# Sheet2.net
KiCad netlist of a schematic drawn in Altium Designer
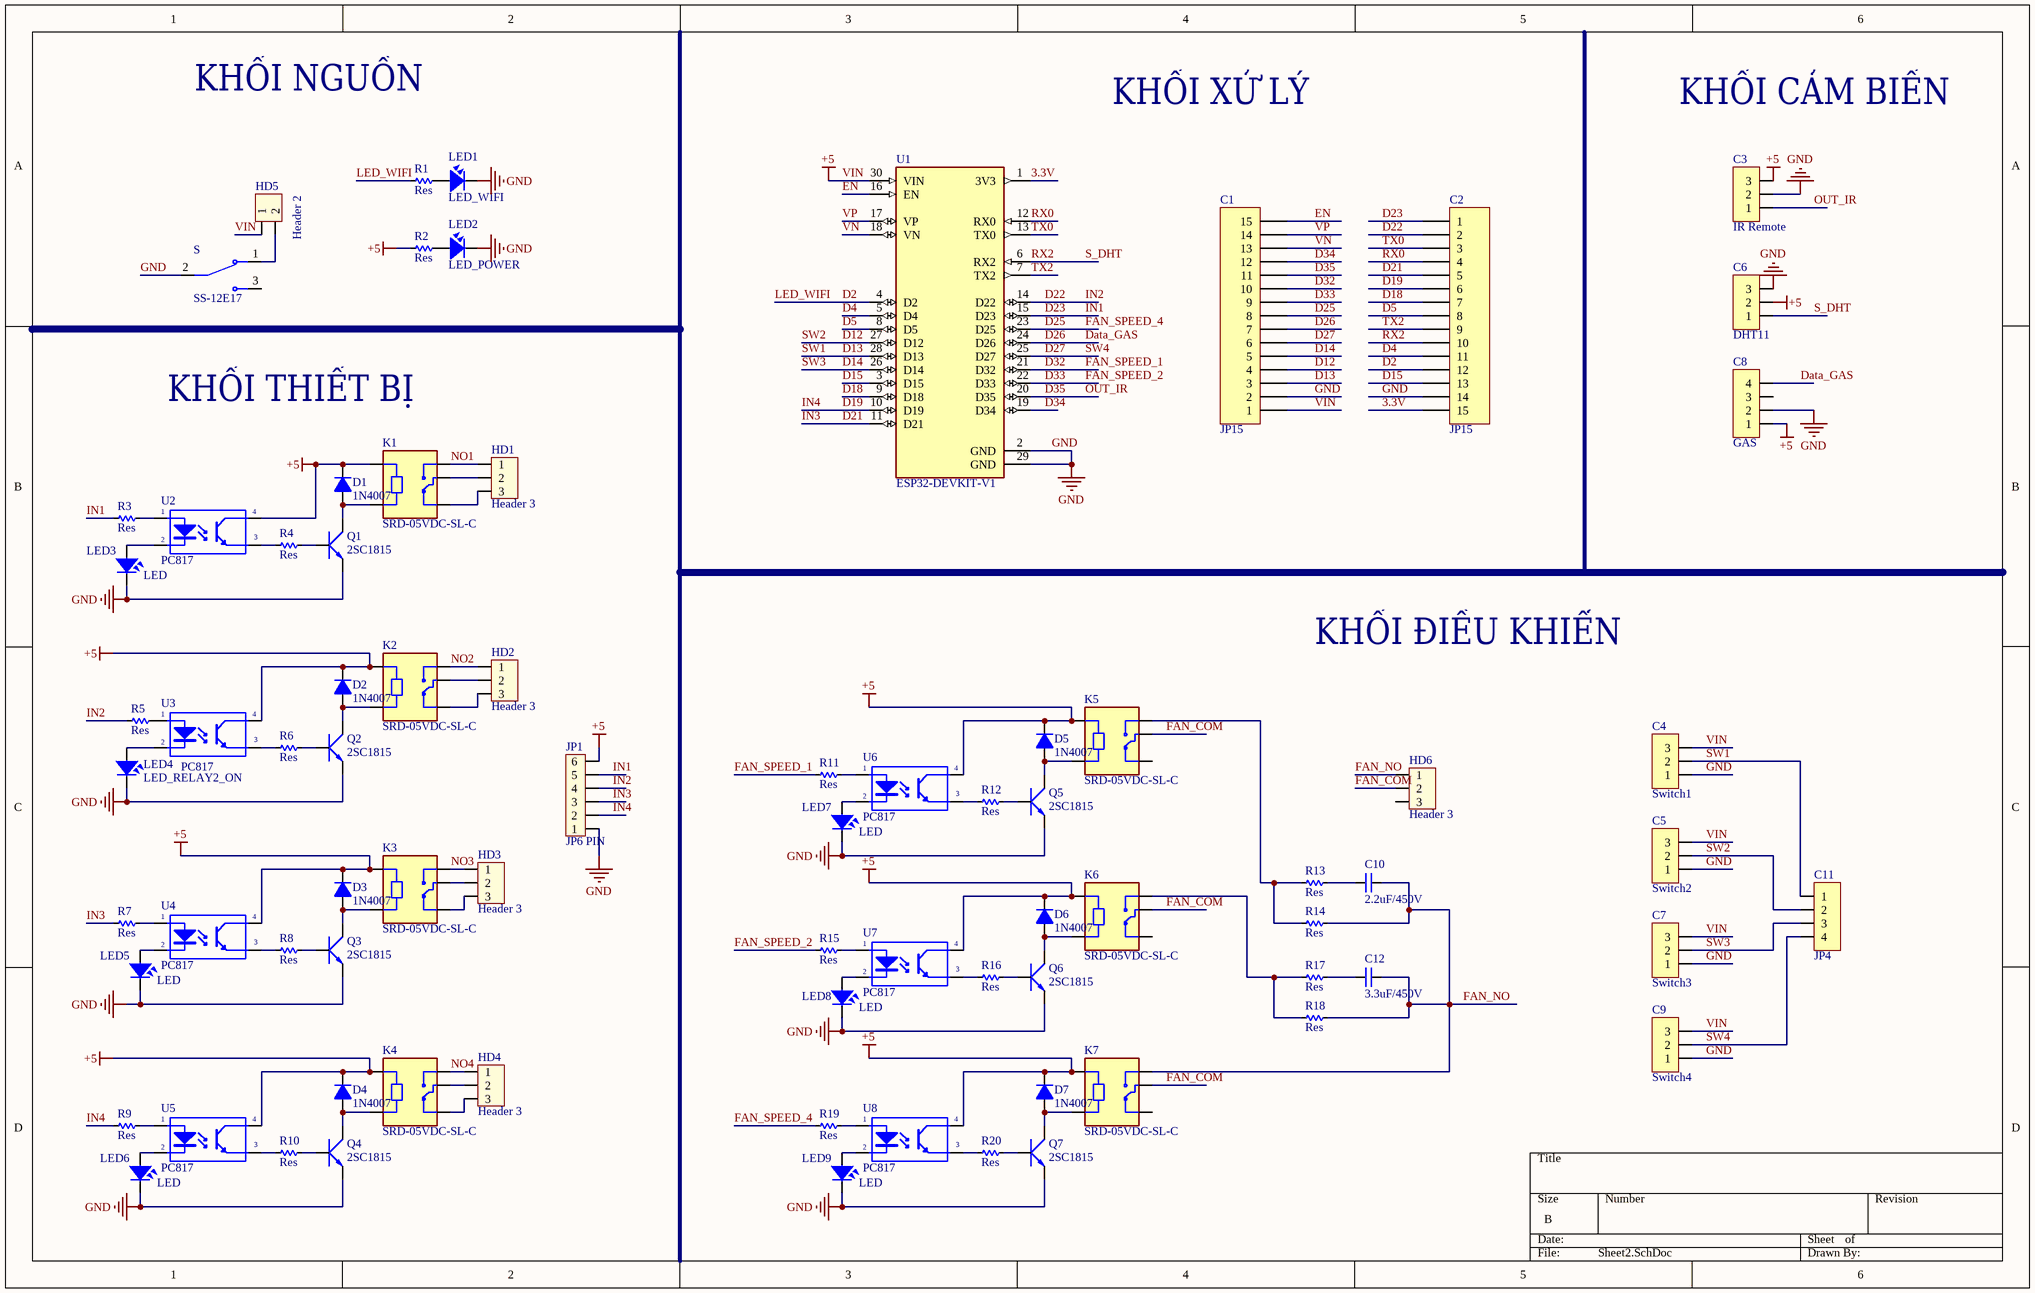
[diagram p0: Sheet2.SchDoc]

(export (version "E")
  (design (tool "Eeschema 10.0.6"))
  (components
    (comp (ref "C1")
      (value "JP15")
      (footprint "JP15-C1T")
      (description "WR-PHD 2.54 mm Angled Socket Header")
      (fields
        (field (name "MANUFACTURER") "Würth Elektronik eiSos GmbH")
        (field (name "PARTNO") "613015143121")
        (field (name "CREATED BY") "Karrer Zheng")
      )
      (libsource (lib "TechMT.VN_Lib_Project v2") (part "JP15"))
    )
    (comp (ref "C2")
      (value "JP15")
      (footprint "JP15-C1T")
      (description "WR-PHD 2.54 mm Angled Socket Header")
      (fields
        (field (name "MANUFACTURER") "Würth Elektronik eiSos GmbH")
        (field (name "PARTNO") "613015143121")
        (field (name "CREATED BY") "Karrer Zheng")
      )
      (libsource (lib "") (part "JP15_1"))
    )
    (comp (ref "C3")
      (value "IR Remote")
      (footprint "JP3-C1T")
      (description "WR-PHD 2.54 mm Angled Socket Header")
      (fields
        (field (name "MANUFACTURER") "Würth Elektronik eiSos GmbH")
        (field (name "PARTNO") "613003143121")
        (field (name "CREATED BY") "Karrer Zheng")
      )
      (libsource (lib "TechMT.VN_Lib_Project v2") (part "JP3"))
    )
    (comp (ref "C4")
      (value "Switch1")
      (footprint "JP3-C1T")
      (description "WR-PHD 2.54 mm Angled Socket Header")
      (fields
        (field (name "MANUFACTURER") "Würth Elektronik eiSos GmbH")
        (field (name "PARTNO") "613003143121")
        (field (name "CREATED BY") "Karrer Zheng")
      )
      (libsource (lib "TechMT.VN_Lib_Project v2") (part "JP3"))
    )
    (comp (ref "C5")
      (value "Switch2")
      (footprint "JP3-C1T")
      (description "WR-PHD 2.54 mm Angled Socket Header")
      (fields
        (field (name "MANUFACTURER") "Würth Elektronik eiSos GmbH")
        (field (name "PARTNO") "613003143121")
        (field (name "CREATED BY") "Karrer Zheng")
      )
      (libsource (lib "TechMT.VN_Lib_Project v2") (part "JP3"))
    )
    (comp (ref "C6")
      (value "DHT11")
      (footprint "JP3-C1T")
      (description "WR-PHD 2.54 mm Angled Socket Header")
      (fields
        (field (name "MANUFACTURER") "Würth Elektronik eiSos GmbH")
        (field (name "PARTNO") "613003143121")
        (field (name "CREATED BY") "Karrer Zheng")
      )
      (libsource (lib "TechMT.VN_Lib_Project v2") (part "JP3"))
    )
    (comp (ref "C7")
      (value "Switch3")
      (footprint "JP3-C1T")
      (description "WR-PHD 2.54 mm Angled Socket Header")
      (fields
        (field (name "MANUFACTURER") "Würth Elektronik eiSos GmbH")
        (field (name "PARTNO") "613003143121")
        (field (name "CREATED BY") "Karrer Zheng")
      )
      (libsource (lib "TechMT.VN_Lib_Project v2") (part "JP3"))
    )
    (comp (ref "C8")
      (value "GAS")
      (footprint "JP4-C1T")
      (description "WR-PHD 2.54 mm Angled Socket Header")
      (fields
        (field (name "MANUFACTURER") "Würth Elektronik eiSos GmbH")
        (field (name "PARTNO") "613004143121")
        (field (name "CREATED BY") "Karrer Zheng")
      )
      (libsource (lib "TechMT.VN_Lib_Project v2") (part "JP4"))
    )
    (comp (ref "C9")
      (value "Switch4")
      (footprint "JP3-C1T")
      (description "WR-PHD 2.54 mm Angled Socket Header")
      (fields
        (field (name "MANUFACTURER") "Würth Elektronik eiSos GmbH")
        (field (name "PARTNO") "613003143121")
        (field (name "CREATED BY") "Karrer Zheng")
      )
      (libsource (lib "TechMT.VN_Lib_Project v2") (part "JP3"))
    )
    (comp (ref "C10")
      (value "2.2uF/450V")
      (footprint "Capacitor_CBB")
      (description "Cap 10000uF/63V")
      (libsource (lib "syhaunguyen") (part "CP9"))
    )
    (comp (ref "C11")
      (value "JP4")
      (footprint "JP4-C1T")
      (description "WR-PHD 2.54 mm Angled Socket Header")
      (fields
        (field (name "MANUFACTURER") "Würth Elektronik eiSos GmbH")
        (field (name "PARTNO") "613004143121")
        (field (name "CREATED BY") "Karrer Zheng")
      )
      (libsource (lib "") (part "JP4_1"))
    )
    (comp (ref "C12")
      (value "3.3uF/450V")
      (footprint "Capacitor_CBB")
      (description "Cap 10000uF/63V")
      (libsource (lib "syhaunguyen") (part "CP9"))
    )
    (comp (ref "D1")
      (value "1N4007")
      (footprint "D1A")
      (description "Diode 1A")
      (libsource (lib "syhaunguyen") (part "D1A"))
    )
    (comp (ref "D2")
      (value "1N4007")
      (footprint "D1A")
      (description "Diode 1A")
      (libsource (lib "syhaunguyen") (part "D1A"))
    )
    (comp (ref "D3")
      (value "1N4007")
      (footprint "D1A")
      (description "Diode 1A")
      (libsource (lib "syhaunguyen") (part "D1A"))
    )
    (comp (ref "D4")
      (value "1N4007")
      (footprint "D1A")
      (description "Diode 1A")
      (libsource (lib "syhaunguyen") (part "D1A"))
    )
    (comp (ref "D5")
      (value "1N4007")
      (footprint "D1A")
      (description "Diode 1A")
      (libsource (lib "syhaunguyen") (part "D1A"))
    )
    (comp (ref "D6")
      (value "1N4007")
      (footprint "D1A")
      (description "Diode 1A")
      (libsource (lib "syhaunguyen") (part "D1A"))
    )
    (comp (ref "D7")
      (value "1N4007")
      (footprint "D1A")
      (description "Diode 1A")
      (libsource (lib "syhaunguyen") (part "D1A"))
    )
    (comp (ref "HD1")
      (value "Header 3")
      (footprint "HED3")
      (description "Header 3 (Green)")
      (libsource (lib "syhaunguyen") (part "Hed3"))
    )
    (comp (ref "HD2")
      (value "Header 3")
      (footprint "HED3")
      (description "Header 3 (Green)")
      (libsource (lib "syhaunguyen") (part "Hed3"))
    )
    (comp (ref "HD3")
      (value "Header 3")
      (footprint "HED3")
      (description "Header 3 (Green)")
      (libsource (lib "syhaunguyen") (part "Hed3"))
    )
    (comp (ref "HD4")
      (value "Header 3")
      (footprint "HED3")
      (description "Header 3 (Green)")
      (libsource (lib "syhaunguyen") (part "Hed3"))
    )
    (comp (ref "HD5")
      (value "Header 2")
      (footprint "HED2")
      (description "Header 2 (Green)")
      (libsource (lib "syhaunguyen") (part "Hed2"))
    )
    (comp (ref "HD6")
      (value "Header 3")
      (footprint "HED3")
      (description "Header 3 (Green)")
      (libsource (lib "syhaunguyen") (part "Hed3"))
    )
    (comp (ref "JP1") (value "JP6 PIN") (footprint "JP6") (libsource (lib "syhaunguyen") (part "JP6")))
    (comp (ref "K1")
      (value "SRD-05VDC-SL-C")
      (footprint "RELAY_SRD-05VDC-SL-C")
      (fields (field (name "MF") "Songle Relay"))
      (libsource (lib "SRD-05VDC-SL-C") (part "SRD-05VDC-SL-C"))
    )
    (comp (ref "K2")
      (value "SRD-05VDC-SL-C")
      (footprint "RELAY_SRD-05VDC-SL-C")
      (fields (field (name "MF") "Songle Relay"))
      (libsource (lib "SRD-05VDC-SL-C") (part "SRD-05VDC-SL-C"))
    )
    (comp (ref "K3")
      (value "SRD-05VDC-SL-C")
      (footprint "RELAY_SRD-05VDC-SL-C")
      (fields (field (name "MF") "Songle Relay"))
      (libsource (lib "SRD-05VDC-SL-C") (part "SRD-05VDC-SL-C"))
    )
    (comp (ref "K4")
      (value "SRD-05VDC-SL-C")
      (footprint "RELAY_SRD-05VDC-SL-C")
      (fields (field (name "MF") "Songle Relay"))
      (libsource (lib "SRD-05VDC-SL-C") (part "SRD-05VDC-SL-C"))
    )
    (comp (ref "K5")
      (value "SRD-05VDC-SL-C")
      (footprint "RELAY_SRD-05VDC-SL-C")
      (fields (field (name "MF") "Songle Relay"))
      (libsource (lib "SRD-05VDC-SL-C") (part "SRD-05VDC-SL-C"))
    )
    (comp (ref "K6")
      (value "SRD-05VDC-SL-C")
      (footprint "RELAY_SRD-05VDC-SL-C")
      (fields (field (name "MF") "Songle Relay"))
      (libsource (lib "SRD-05VDC-SL-C") (part "SRD-05VDC-SL-C"))
    )
    (comp (ref "K7")
      (value "SRD-05VDC-SL-C")
      (footprint "RELAY_SRD-05VDC-SL-C")
      (fields (field (name "MF") "Songle Relay"))
      (libsource (lib "SRD-05VDC-SL-C") (part "SRD-05VDC-SL-C"))
    )
    (comp (ref "LED1")
      (value "LED_WIFI")
      (footprint "LED-5 GRe")
      (description "LED Single colour Green and Red")
      (libsource (lib "syhaunguyen") (part "LED"))
    )
    (comp (ref "LED2")
      (value "LED_POWER")
      (footprint "LED-5 GRe")
      (description "LED Single colour Green and Red")
      (libsource (lib "syhaunguyen") (part "LED"))
    )
    (comp (ref "LED3")
      (value "LED")
      (footprint "LED-5 GRe")
      (description "LED Single colour Green and Red")
      (libsource (lib "syhaunguyen") (part "LED"))
    )
    (comp (ref "LED4")
      (value "LED_RELAY2_ON")
      (footprint "LED-5 GRe")
      (description "LED Single colour Green and Red")
      (libsource (lib "syhaunguyen") (part "LED"))
    )
    (comp (ref "LED5")
      (value "LED")
      (footprint "LED-5 GRe")
      (description "LED Single colour Green and Red")
      (libsource (lib "syhaunguyen") (part "LED"))
    )
    (comp (ref "LED6")
      (value "LED")
      (footprint "LED-5 GRe")
      (description "LED Single colour Green and Red")
      (libsource (lib "syhaunguyen") (part "LED"))
    )
    (comp (ref "LED7")
      (value "LED")
      (footprint "LED-5 GRe")
      (description "LED Single colour Green and Red")
      (libsource (lib "syhaunguyen") (part "LED"))
    )
    (comp (ref "LED8")
      (value "LED")
      (footprint "LED-5 GRe")
      (description "LED Single colour Green and Red")
      (libsource (lib "syhaunguyen") (part "LED"))
    )
    (comp (ref "LED9")
      (value "LED")
      (footprint "LED-5 GRe")
      (description "LED Single colour Green and Red")
      (libsource (lib "syhaunguyen") (part "LED"))
    )
    (comp (ref "Q1")
      (value "2SC1815")
      (footprint "TO92-123")
      (description "NPN 600mW, ECB")
      (libsource (lib "TechMT.VN_Lib_Project v2") (part "2SC1815"))
    )
    (comp (ref "Q2")
      (value "2SC1815")
      (footprint "TO92-123")
      (description "NPN 600mW, ECB")
      (libsource (lib "TechMT.VN_Lib_Project v2") (part "2SC1815"))
    )
    (comp (ref "Q3")
      (value "2SC1815")
      (footprint "TO92-123")
      (description "NPN 600mW, ECB")
      (libsource (lib "TechMT.VN_Lib_Project v2") (part "2SC1815"))
    )
    (comp (ref "Q4")
      (value "2SC1815")
      (footprint "TO92-123")
      (description "NPN 600mW, ECB")
      (libsource (lib "TechMT.VN_Lib_Project v2") (part "2SC1815"))
    )
    (comp (ref "Q5")
      (value "2SC1815")
      (footprint "TO92-123")
      (description "NPN 600mW, ECB")
      (libsource (lib "TechMT.VN_Lib_Project v2") (part "2SC1815"))
    )
    (comp (ref "Q6")
      (value "2SC1815")
      (footprint "TO92-123")
      (description "NPN 600mW, ECB")
      (libsource (lib "TechMT.VN_Lib_Project v2") (part "2SC1815"))
    )
    (comp (ref "Q7")
      (value "2SC1815")
      (footprint "TO92-123")
      (description "NPN 600mW, ECB")
      (libsource (lib "TechMT.VN_Lib_Project v2") (part "2SC1815"))
    )
    (comp (ref "R1")
      (value "Res")
      (footprint "RES-1/4W")
      (fields
        (field (name "MANUFACTURER") "Generic Components")
        (field (name "PUBLISHER") "Altium Hobart Technology Centre")
      )
      (libsource (lib "TechMT.VN_Lib_Project v2") (part "Res"))
    )
    (comp (ref "R2")
      (value "Res")
      (footprint "RES-1/4W")
      (fields
        (field (name "MANUFACTURER") "Generic Components")
        (field (name "PUBLISHER") "Altium Hobart Technology Centre")
      )
      (libsource (lib "TechMT.VN_Lib_Project v2") (part "Res"))
    )
    (comp (ref "R3")
      (value "Res")
      (footprint "RES-1/4W")
      (fields
        (field (name "MANUFACTURER") "Generic Components")
        (field (name "PUBLISHER") "Altium Hobart Technology Centre")
      )
      (libsource (lib "TechMT.VN_Lib_Project v2") (part "Res"))
    )
    (comp (ref "R4")
      (value "Res")
      (footprint "RES-1/4W")
      (fields
        (field (name "MANUFACTURER") "Generic Components")
        (field (name "PUBLISHER") "Altium Hobart Technology Centre")
      )
      (libsource (lib "TechMT.VN_Lib_Project v2") (part "Res"))
    )
    (comp (ref "R5")
      (value "Res")
      (footprint "RES-1/4W")
      (fields
        (field (name "MANUFACTURER") "Generic Components")
        (field (name "PUBLISHER") "Altium Hobart Technology Centre")
      )
      (libsource (lib "TechMT.VN_Lib_Project v2") (part "Res"))
    )
    (comp (ref "R6")
      (value "Res")
      (footprint "RES-1/4W")
      (fields
        (field (name "MANUFACTURER") "Generic Components")
        (field (name "PUBLISHER") "Altium Hobart Technology Centre")
      )
      (libsource (lib "TechMT.VN_Lib_Project v2") (part "Res"))
    )
    (comp (ref "R7")
      (value "Res")
      (footprint "RES-1/4W")
      (fields
        (field (name "MANUFACTURER") "Generic Components")
        (field (name "PUBLISHER") "Altium Hobart Technology Centre")
      )
      (libsource (lib "TechMT.VN_Lib_Project v2") (part "Res"))
    )
    (comp (ref "R8")
      (value "Res")
      (footprint "RES-1/4W")
      (fields
        (field (name "MANUFACTURER") "Generic Components")
        (field (name "PUBLISHER") "Altium Hobart Technology Centre")
      )
      (libsource (lib "TechMT.VN_Lib_Project v2") (part "Res"))
    )
    (comp (ref "R9")
      (value "Res")
      (footprint "RES-1/4W")
      (fields
        (field (name "MANUFACTURER") "Generic Components")
        (field (name "PUBLISHER") "Altium Hobart Technology Centre")
      )
      (libsource (lib "TechMT.VN_Lib_Project v2") (part "Res"))
    )
    (comp (ref "R10")
      (value "Res")
      (footprint "RES-1/4W")
      (fields
        (field (name "MANUFACTURER") "Generic Components")
        (field (name "PUBLISHER") "Altium Hobart Technology Centre")
      )
      (libsource (lib "TechMT.VN_Lib_Project v2") (part "Res"))
    )
    (comp (ref "R11")
      (value "Res")
      (footprint "RES-1/4W")
      (fields
        (field (name "MANUFACTURER") "Generic Components")
        (field (name "PUBLISHER") "Altium Hobart Technology Centre")
      )
      (libsource (lib "TechMT.VN_Lib_Project v2") (part "Res"))
    )
    (comp (ref "R12")
      (value "Res")
      (footprint "RES-1/4W")
      (fields
        (field (name "MANUFACTURER") "Generic Components")
        (field (name "PUBLISHER") "Altium Hobart Technology Centre")
      )
      (libsource (lib "TechMT.VN_Lib_Project v2") (part "Res"))
    )
    (comp (ref "R13")
      (value "Res")
      (footprint "RES-1/4W")
      (fields
        (field (name "MANUFACTURER") "Generic Components")
        (field (name "PUBLISHER") "Altium Hobart Technology Centre")
      )
      (libsource (lib "TechMT.VN_Lib_Project v2") (part "Res"))
    )
    (comp (ref "R14")
      (value "Res")
      (footprint "RES-1/4W")
      (fields
        (field (name "MANUFACTURER") "Generic Components")
        (field (name "PUBLISHER") "Altium Hobart Technology Centre")
      )
      (libsource (lib "TechMT.VN_Lib_Project v2") (part "Res"))
    )
    (comp (ref "R15")
      (value "Res")
      (footprint "RES-1/4W")
      (fields
        (field (name "MANUFACTURER") "Generic Components")
        (field (name "PUBLISHER") "Altium Hobart Technology Centre")
      )
      (libsource (lib "TechMT.VN_Lib_Project v2") (part "Res"))
    )
    (comp (ref "R16")
      (value "Res")
      (footprint "RES-1/4W")
      (fields
        (field (name "MANUFACTURER") "Generic Components")
        (field (name "PUBLISHER") "Altium Hobart Technology Centre")
      )
      (libsource (lib "TechMT.VN_Lib_Project v2") (part "Res"))
    )
    (comp (ref "R17")
      (value "Res")
      (footprint "RES-1/4W")
      (fields
        (field (name "MANUFACTURER") "Generic Components")
        (field (name "PUBLISHER") "Altium Hobart Technology Centre")
      )
      (libsource (lib "TechMT.VN_Lib_Project v2") (part "Res"))
    )
    (comp (ref "R18")
      (value "Res")
      (footprint "RES-1/4W")
      (fields
        (field (name "MANUFACTURER") "Generic Components")
        (field (name "PUBLISHER") "Altium Hobart Technology Centre")
      )
      (libsource (lib "TechMT.VN_Lib_Project v2") (part "Res"))
    )
    (comp (ref "R19")
      (value "Res")
      (footprint "RES-1/4W")
      (fields
        (field (name "MANUFACTURER") "Generic Components")
        (field (name "PUBLISHER") "Altium Hobart Technology Centre")
      )
      (libsource (lib "TechMT.VN_Lib_Project v2") (part "Res"))
    )
    (comp (ref "R20")
      (value "Res")
      (footprint "RES-1/4W")
      (fields
        (field (name "MANUFACTURER") "Generic Components")
        (field (name "PUBLISHER") "Altium Hobart Technology Centre")
      )
      (libsource (lib "TechMT.VN_Lib_Project v2") (part "Res"))
    )
    (comp (ref "S")
      (value "SS-12E17")
      (footprint "SW_SS-12E17")
      (description "3-Pin SPDT Slide Switch")
      (fields (field (name "MF") "Jameco Valuepro"))
      (libsource (lib "Cong_Tac_Gat_3_chan") (part "SS-12E17"))
    )
    (comp (ref "U1")
      (value "ESP32-DEVKIT-V1")
      (footprint "MODULE_ESP32_DEVKIT_V1")
      (fields (field (name "MF") "Do it"))
      (libsource (lib "ESP32-DEVKIT-V1") (part "ESP32-DEVKIT-V1"))
    )
    (comp (ref "U2")
      (value "PC817")
      (footprint "DIP4/W0.3")
      (description "Single Opto")
      (libsource (lib "syhaunguyen") (part "PC817"))
    )
    (comp (ref "U3")
      (value "PC817")
      (footprint "DIP4/W0.3")
      (description "Single Opto")
      (libsource (lib "syhaunguyen") (part "PC817"))
    )
    (comp (ref "U4")
      (value "PC817")
      (footprint "DIP4/W0.3")
      (description "Single Opto")
      (libsource (lib "syhaunguyen") (part "PC817"))
    )
    (comp (ref "U5")
      (value "PC817")
      (footprint "DIP4/W0.3")
      (description "Single Opto")
      (libsource (lib "syhaunguyen") (part "PC817"))
    )
    (comp (ref "U6")
      (value "PC817")
      (footprint "DIP4/W0.3")
      (description "Single Opto")
      (libsource (lib "syhaunguyen") (part "PC817"))
    )
    (comp (ref "U7")
      (value "PC817")
      (footprint "DIP4/W0.3")
      (description "Single Opto")
      (libsource (lib "syhaunguyen") (part "PC817"))
    )
    (comp (ref "U8")
      (value "PC817")
      (footprint "DIP4/W0.3")
      (description "Single Opto")
      (libsource (lib "syhaunguyen") (part "PC817"))
    )
  )
  (nets
    (net (code "1") (name "+5") (class "Default")
      (node (ref "C1") (pin "1") (pinfunction "1_1") (pintype "passive"))
      (node (ref "C3") (pin "3") (pinfunction "3_3") (pintype "passive"))
      (node (ref "C4") (pin "3") (pinfunction "3_3") (pintype "passive"))
      (node (ref "C5") (pin "3") (pinfunction "3_3") (pintype "passive"))
      (node (ref "C6") (pin "2") (pinfunction "2_2") (pintype "passive"))
      (node (ref "C7") (pin "3") (pinfunction "3_3") (pintype "passive"))
      (node (ref "C8") (pin "1") (pinfunction "1_1") (pintype "passive"))
      (node (ref "C9") (pin "3") (pinfunction "3_3") (pintype "passive"))
      (node (ref "D1") (pin "2") (pinfunction "K_2") (pintype "passive"))
      (node (ref "D2") (pin "2") (pinfunction "K_2") (pintype "passive"))
      (node (ref "D3") (pin "2") (pinfunction "K_2") (pintype "passive"))
      (node (ref "D4") (pin "2") (pinfunction "K_2") (pintype "passive"))
      (node (ref "D5") (pin "2") (pinfunction "K_2") (pintype "passive"))
      (node (ref "D6") (pin "2") (pinfunction "K_2") (pintype "passive"))
      (node (ref "D7") (pin "2") (pinfunction "K_2") (pintype "passive"))
      (node (ref "HD5") (pin "1") (pinfunction "1_1") (pintype "passive"))
      (node (ref "JP1") (pin "6") (pinfunction "6_6") (pintype "passive"))
      (node (ref "K1") (pin "A1") (pinfunction "A1_A1") (pintype "passive"))
      (node (ref "K2") (pin "A1") (pinfunction "A1_A1") (pintype "passive"))
      (node (ref "K3") (pin "A1") (pinfunction "A1_A1") (pintype "passive"))
      (node (ref "K4") (pin "A1") (pinfunction "A1_A1") (pintype "passive"))
      (node (ref "K5") (pin "A1") (pinfunction "A1_A1") (pintype "passive"))
      (node (ref "K6") (pin "A1") (pinfunction "A1_A1") (pintype "passive"))
      (node (ref "K7") (pin "A1") (pinfunction "A1_A1") (pintype "passive"))
      (node (ref "R2") (pin "2") (pinfunction "2_2") (pintype "passive"))
      (node (ref "U1") (pin "30") (pinfunction "VIN_30") (pintype "input"))
      (node (ref "U2") (pin "4") (pinfunction "C_4") (pintype "passive"))
      (node (ref "U3") (pin "4") (pinfunction "C_4") (pintype "passive"))
      (node (ref "U4") (pin "4") (pinfunction "C_4") (pintype "passive"))
      (node (ref "U5") (pin "4") (pinfunction "C_4") (pintype "passive"))
      (node (ref "U6") (pin "4") (pinfunction "C_4") (pintype "passive"))
      (node (ref "U7") (pin "4") (pinfunction "C_4") (pintype "passive"))
      (node (ref "U8") (pin "4") (pinfunction "C_4") (pintype "passive"))
    )
    (net (code "2") (name "/3.3V") (class "Default")
      (node (ref "C2") (pin "15") (pinfunction "15_15") (pintype "passive"))
      (node (ref "U1") (pin "1") (pinfunction "3V3_1") (pintype "output"))
    )
    (net (code "4") (name "/D2") (class "Default")
      (node (ref "C2") (pin "12") (pinfunction "12_12") (pintype "passive"))
      (node (ref "R1") (pin "2") (pinfunction "2_2") (pintype "passive"))
      (node (ref "U1") (pin "4") (pinfunction "D2_4") (pintype "bidirectional"))
    )
    (net (code "5") (name "/D4") (class "Default")
      (node (ref "C2") (pin "11") (pinfunction "11_11") (pintype "passive"))
      (node (ref "U1") (pin "5") (pinfunction "D4_5") (pintype "bidirectional"))
    )
    (net (code "6") (name "/D5") (class "Default")
      (node (ref "C2") (pin "8") (pinfunction "8_8") (pintype "passive"))
      (node (ref "U1") (pin "8") (pinfunction "D5_8") (pintype "bidirectional"))
    )
    (net (code "7") (name "/D12") (class "Default")
      (node (ref "C1") (pin "4") (pinfunction "4_4") (pintype "passive"))
      (node (ref "C11") (pin "2") (pinfunction "2_2") (pintype "passive"))
      (node (ref "C5") (pin "2") (pinfunction "2_2") (pintype "passive"))
      (node (ref "U1") (pin "27") (pinfunction "D12_27") (pintype "bidirectional"))
    )
    (net (code "8") (name "/D13") (class "Default")
      (node (ref "C1") (pin "3") (pinfunction "3_3") (pintype "passive"))
      (node (ref "C11") (pin "1") (pinfunction "1_1") (pintype "passive"))
      (node (ref "C4") (pin "2") (pinfunction "2_2") (pintype "passive"))
      (node (ref "U1") (pin "28") (pinfunction "D13_28") (pintype "bidirectional"))
    )
    (net (code "9") (name "/D14") (class "Default")
      (node (ref "C1") (pin "5") (pinfunction "5_5") (pintype "passive"))
      (node (ref "C11") (pin "3") (pinfunction "3_3") (pintype "passive"))
      (node (ref "C7") (pin "2") (pinfunction "2_2") (pintype "passive"))
      (node (ref "U1") (pin "26") (pinfunction "D14_26") (pintype "bidirectional"))
    )
    (net (code "10") (name "/D15") (class "Default")
      (node (ref "C2") (pin "13") (pinfunction "13_13") (pintype "passive"))
      (node (ref "U1") (pin "3") (pinfunction "D15_3") (pintype "bidirectional"))
    )
    (net (code "11") (name "/D18") (class "Default")
      (node (ref "C2") (pin "7") (pinfunction "7_7") (pintype "passive"))
      (node (ref "U1") (pin "9") (pinfunction "D18_9") (pintype "bidirectional"))
    )
    (net (code "12") (name "/D19") (class "Default")
      (node (ref "C2") (pin "6") (pinfunction "6_6") (pintype "passive"))
      (node (ref "JP1") (pin "2") (pinfunction "2_2") (pintype "passive"))
      (node (ref "R9") (pin "2") (pinfunction "2_2") (pintype "passive"))
      (node (ref "U1") (pin "10") (pinfunction "D19_10") (pintype "bidirectional"))
    )
    (net (code "13") (name "/D21") (class "Default")
      (node (ref "C2") (pin "5") (pinfunction "5_5") (pintype "passive"))
      (node (ref "JP1") (pin "3") (pinfunction "3_3") (pintype "passive"))
      (node (ref "R7") (pin "2") (pinfunction "2_2") (pintype "passive"))
      (node (ref "U1") (pin "11") (pinfunction "D21_11") (pintype "bidirectional"))
    )
    (net (code "14") (name "/D22") (class "Default")
      (node (ref "C2") (pin "2") (pinfunction "2_2") (pintype "passive"))
      (node (ref "JP1") (pin "4") (pinfunction "4_4") (pintype "passive"))
      (node (ref "R5") (pin "2") (pinfunction "2_2") (pintype "passive"))
      (node (ref "U1") (pin "14") (pinfunction "D22_14") (pintype "bidirectional"))
    )
    (net (code "15") (name "/D23") (class "Default")
      (node (ref "C2") (pin "1") (pinfunction "1_1") (pintype "passive"))
      (node (ref "JP1") (pin "5") (pinfunction "5_5") (pintype "passive"))
      (node (ref "R3") (pin "2") (pinfunction "2_2") (pintype "passive"))
      (node (ref "U1") (pin "15") (pinfunction "D23_15") (pintype "bidirectional"))
    )
    (net (code "16") (name "/D25") (class "Default")
      (node (ref "C1") (pin "8") (pinfunction "8_8") (pintype "passive"))
      (node (ref "R19") (pin "1") (pinfunction "1_1") (pintype "passive"))
      (node (ref "U1") (pin "23") (pinfunction "D25_23") (pintype "bidirectional"))
    )
    (net (code "17") (name "/D26") (class "Default")
      (node (ref "C1") (pin "7") (pinfunction "7_7") (pintype "passive"))
      (node (ref "C8") (pin "4") (pinfunction "4_4") (pintype "passive"))
      (node (ref "U1") (pin "24") (pinfunction "D26_24") (pintype "bidirectional"))
    )
    (net (code "18") (name "/D27") (class "Default")
      (node (ref "C1") (pin "6") (pinfunction "6_6") (pintype "passive"))
      (node (ref "C11") (pin "4") (pinfunction "4_4") (pintype "passive"))
      (node (ref "C9") (pin "2") (pinfunction "2_2") (pintype "passive"))
      (node (ref "U1") (pin "25") (pinfunction "D27_25") (pintype "bidirectional"))
    )
    (net (code "19") (name "/D32") (class "Default")
      (node (ref "C1") (pin "10") (pinfunction "10_10") (pintype "passive"))
      (node (ref "R11") (pin "1") (pinfunction "1_1") (pintype "passive"))
      (node (ref "U1") (pin "21") (pinfunction "D32_21") (pintype "bidirectional"))
    )
    (net (code "20") (name "/D33") (class "Default")
      (node (ref "C1") (pin "9") (pinfunction "9_9") (pintype "passive"))
      (node (ref "R15") (pin "1") (pinfunction "1_1") (pintype "passive"))
      (node (ref "U1") (pin "22") (pinfunction "D33_22") (pintype "bidirectional"))
    )
    (net (code "21") (name "/D34") (class "Default")
      (node (ref "C1") (pin "12") (pinfunction "12_12") (pintype "passive"))
      (node (ref "U1") (pin "19") (pinfunction "D34_19") (pintype "bidirectional"))
    )
    (net (code "22") (name "/D35") (class "Default")
      (node (ref "C1") (pin "11") (pinfunction "11_11") (pintype "passive"))
      (node (ref "C3") (pin "1") (pinfunction "1_1") (pintype "passive"))
      (node (ref "U1") (pin "20") (pinfunction "D35_20") (pintype "bidirectional"))
    )
    (net (code "23") (name "/EN") (class "Default")
      (node (ref "C1") (pin "15") (pinfunction "15_15") (pintype "passive"))
      (node (ref "U1") (pin "16") (pinfunction "EN_16") (pintype "input"))
    )
    (net (code "24") (name "/FAN_COM") (class "Default")
      (node (ref "HD6") (pin "2") (pinfunction "2_2") (pintype "passive"))
      (node (ref "K5") (pin "COM") (pinfunction "COM_COM") (pintype "passive"))
      (node (ref "K6") (pin "COM") (pinfunction "COM_COM") (pintype "passive"))
      (node (ref "K7") (pin "COM") (pinfunction "COM_COM") (pintype "passive"))
    )
    (net (code "25") (name "/FAN_NO") (class "Default")
      (node (ref "C10") (pin "1") (pinfunction "1_1") (pintype "passive"))
      (node (ref "C12") (pin "1") (pinfunction "1_1") (pintype "passive"))
      (node (ref "HD6") (pin "1") (pinfunction "1_1") (pintype "passive"))
      (node (ref "K7") (pin "NO") (pinfunction "NO_NO") (pintype "passive"))
      (node (ref "R14") (pin "2") (pinfunction "2_2") (pintype "passive"))
      (node (ref "R18") (pin "2") (pinfunction "2_2") (pintype "passive"))
    )
    (net (code "26") (name "/NO1") (class "Default")
      (node (ref "HD1") (pin "1") (pinfunction "1_1") (pintype "passive"))
      (node (ref "K1") (pin "NO") (pinfunction "NO_NO") (pintype "passive"))
    )
    (net (code "27") (name "/NO2") (class "Default")
      (node (ref "HD2") (pin "1") (pinfunction "1_1") (pintype "passive"))
      (node (ref "K2") (pin "NO") (pinfunction "NO_NO") (pintype "passive"))
    )
    (net (code "28") (name "/NO3") (class "Default")
      (node (ref "HD3") (pin "1") (pinfunction "1_1") (pintype "passive"))
      (node (ref "K3") (pin "NO") (pinfunction "NO_NO") (pintype "passive"))
    )
    (net (code "29") (name "/NO4") (class "Default")
      (node (ref "HD4") (pin "1") (pinfunction "1_1") (pintype "passive"))
      (node (ref "K4") (pin "NO") (pinfunction "NO_NO") (pintype "passive"))
    )
    (net (code "30") (name "/RX0") (class "Default")
      (node (ref "C2") (pin "4") (pinfunction "4_4") (pintype "passive"))
      (node (ref "U1") (pin "12") (pinfunction "RX0_12") (pintype "input"))
    )
    (net (code "31") (name "/RX2") (class "Default")
      (node (ref "C2") (pin "10") (pinfunction "10_10") (pintype "passive"))
      (node (ref "C6") (pin "1") (pinfunction "1_1") (pintype "passive"))
      (node (ref "U1") (pin "6") (pinfunction "RX2_6") (pintype "input"))
    )
    (net (code "32") (name "/TX0") (class "Default")
      (node (ref "C2") (pin "3") (pinfunction "3_3") (pintype "passive"))
      (node (ref "U1") (pin "13") (pinfunction "TX0_13") (pintype "output"))
    )
    (net (code "33") (name "/TX2") (class "Default")
      (node (ref "C2") (pin "9") (pinfunction "9_9") (pintype "passive"))
      (node (ref "U1") (pin "7") (pinfunction "TX2_7") (pintype "output"))
    )
    (net (code "34") (name "/VN") (class "Default")
      (node (ref "C1") (pin "13") (pinfunction "13_13") (pintype "passive"))
      (node (ref "U1") (pin "18") (pinfunction "VN_18") (pintype "bidirectional"))
    )
    (net (code "35") (name "/VP") (class "Default")
      (node (ref "C1") (pin "14") (pinfunction "14_14") (pintype "passive"))
      (node (ref "U1") (pin "17") (pinfunction "VP_17") (pintype "bidirectional"))
    )
    (net (code "36") (name "GND") (class "Default")
      (node (ref "C1") (pin "2") (pinfunction "2_2") (pintype "passive"))
      (node (ref "C2") (pin "14") (pinfunction "14_14") (pintype "passive"))
      (node (ref "C3") (pin "2") (pinfunction "2_2") (pintype "passive"))
      (node (ref "C4") (pin "1") (pinfunction "1_1") (pintype "passive"))
      (node (ref "C5") (pin "1") (pinfunction "1_1") (pintype "passive"))
      (node (ref "C6") (pin "3") (pinfunction "3_3") (pintype "passive"))
      (node (ref "C7") (pin "1") (pinfunction "1_1") (pintype "passive"))
      (node (ref "C8") (pin "2") (pinfunction "2_2") (pintype "passive"))
      (node (ref "C9") (pin "1") (pinfunction "1_1") (pintype "passive"))
      (node (ref "JP1") (pin "1") (pinfunction "1_1") (pintype "passive"))
      (node (ref "LED1") (pin "2") (pinfunction "2_2") (pintype "passive"))
      (node (ref "LED2") (pin "2") (pinfunction "2_2") (pintype "passive"))
      (node (ref "LED3") (pin "2") (pinfunction "2_2") (pintype "passive"))
      (node (ref "LED4") (pin "2") (pinfunction "2_2") (pintype "passive"))
      (node (ref "LED5") (pin "2") (pinfunction "2_2") (pintype "passive"))
      (node (ref "LED6") (pin "2") (pinfunction "2_2") (pintype "passive"))
      (node (ref "LED7") (pin "2") (pinfunction "2_2") (pintype "passive"))
      (node (ref "LED8") (pin "2") (pinfunction "2_2") (pintype "passive"))
      (node (ref "LED9") (pin "2") (pinfunction "2_2") (pintype "passive"))
      (node (ref "Q1") (pin "1") (pinfunction "E_1") (pintype "passive"))
      (node (ref "Q2") (pin "1") (pinfunction "E_1") (pintype "passive"))
      (node (ref "Q3") (pin "1") (pinfunction "E_1") (pintype "passive"))
      (node (ref "Q4") (pin "1") (pinfunction "E_1") (pintype "passive"))
      (node (ref "Q5") (pin "1") (pinfunction "E_1") (pintype "passive"))
      (node (ref "Q6") (pin "1") (pinfunction "E_1") (pintype "passive"))
      (node (ref "Q7") (pin "1") (pinfunction "E_1") (pintype "passive"))
      (node (ref "S") (pin "2") (pinfunction "2_2") (pintype "passive"))
      (node (ref "U1") (pin "2") (pinfunction "GND_2") (pintype "power_in"))
      (node (ref "U1") (pin "29") (pinfunction "GND_29") (pintype "power_in"))
    )
    (net (code "37") (name "Net-(C10-Pad2)") (class "Default")
      (node (ref "C10") (pin "2") (pinfunction "2_2") (pintype "passive"))
      (node (ref "R13") (pin "2") (pinfunction "2_2") (pintype "passive"))
    )
    (net (code "38") (name "Net-(C12-Pad2)") (class "Default")
      (node (ref "C12") (pin "2") (pinfunction "2_2") (pintype "passive"))
      (node (ref "R17") (pin "2") (pinfunction "2_2") (pintype "passive"))
    )
    (net (code "39") (name "Net-(D1-A)") (class "Default")
      (node (ref "D1") (pin "1") (pinfunction "A_1") (pintype "passive"))
      (node (ref "K1") (pin "A2") (pinfunction "A2_A2") (pintype "passive"))
      (node (ref "Q1") (pin "2") (pinfunction "C_2") (pintype "passive"))
    )
    (net (code "40") (name "Net-(D2-A)") (class "Default")
      (node (ref "D2") (pin "1") (pinfunction "A_1") (pintype "passive"))
      (node (ref "K2") (pin "A2") (pinfunction "A2_A2") (pintype "passive"))
      (node (ref "Q2") (pin "2") (pinfunction "C_2") (pintype "passive"))
    )
    (net (code "41") (name "Net-(D3-A)") (class "Default")
      (node (ref "D3") (pin "1") (pinfunction "A_1") (pintype "passive"))
      (node (ref "K3") (pin "A2") (pinfunction "A2_A2") (pintype "passive"))
      (node (ref "Q3") (pin "2") (pinfunction "C_2") (pintype "passive"))
    )
    (net (code "42") (name "Net-(D4-A)") (class "Default")
      (node (ref "D4") (pin "1") (pinfunction "A_1") (pintype "passive"))
      (node (ref "K4") (pin "A2") (pinfunction "A2_A2") (pintype "passive"))
      (node (ref "Q4") (pin "2") (pinfunction "C_2") (pintype "passive"))
    )
    (net (code "43") (name "Net-(D5-A)") (class "Default")
      (node (ref "D5") (pin "1") (pinfunction "A_1") (pintype "passive"))
      (node (ref "K5") (pin "A2") (pinfunction "A2_A2") (pintype "passive"))
      (node (ref "Q5") (pin "2") (pinfunction "C_2") (pintype "passive"))
    )
    (net (code "44") (name "Net-(D6-A)") (class "Default")
      (node (ref "D6") (pin "1") (pinfunction "A_1") (pintype "passive"))
      (node (ref "K6") (pin "A2") (pinfunction "A2_A2") (pintype "passive"))
      (node (ref "Q6") (pin "2") (pinfunction "C_2") (pintype "passive"))
    )
    (net (code "45") (name "Net-(D7-A)") (class "Default")
      (node (ref "D7") (pin "1") (pinfunction "A_1") (pintype "passive"))
      (node (ref "K7") (pin "A2") (pinfunction "A2_A2") (pintype "passive"))
      (node (ref "Q7") (pin "2") (pinfunction "C_2") (pintype "passive"))
    )
    (net (code "46") (name "Net-(HD1-Pad2)") (class "Default")
      (node (ref "HD1") (pin "2") (pinfunction "2_2") (pintype "passive"))
      (node (ref "K1") (pin "COM") (pinfunction "COM_COM") (pintype "passive"))
    )
    (net (code "47") (name "Net-(HD1-Pad3)") (class "Default")
      (node (ref "HD1") (pin "3") (pinfunction "3_3") (pintype "passive"))
      (node (ref "K1") (pin "NC") (pinfunction "NC_NC") (pintype "passive"))
    )
    (net (code "48") (name "Net-(HD2-Pad2)") (class "Default")
      (node (ref "HD2") (pin "2") (pinfunction "2_2") (pintype "passive"))
      (node (ref "K2") (pin "COM") (pinfunction "COM_COM") (pintype "passive"))
    )
    (net (code "49") (name "Net-(HD2-Pad3)") (class "Default")
      (node (ref "HD2") (pin "3") (pinfunction "3_3") (pintype "passive"))
      (node (ref "K2") (pin "NC") (pinfunction "NC_NC") (pintype "passive"))
    )
    (net (code "50") (name "Net-(HD3-Pad2)") (class "Default")
      (node (ref "HD3") (pin "2") (pinfunction "2_2") (pintype "passive"))
      (node (ref "K3") (pin "COM") (pinfunction "COM_COM") (pintype "passive"))
    )
    (net (code "51") (name "Net-(HD3-Pad3)") (class "Default")
      (node (ref "HD3") (pin "3") (pinfunction "3_3") (pintype "passive"))
      (node (ref "K3") (pin "NC") (pinfunction "NC_NC") (pintype "passive"))
    )
    (net (code "52") (name "Net-(HD4-Pad2)") (class "Default")
      (node (ref "HD4") (pin "2") (pinfunction "2_2") (pintype "passive"))
      (node (ref "K4") (pin "COM") (pinfunction "COM_COM") (pintype "passive"))
    )
    (net (code "53") (name "Net-(HD4-Pad3)") (class "Default")
      (node (ref "HD4") (pin "3") (pinfunction "3_3") (pintype "passive"))
      (node (ref "K4") (pin "NC") (pinfunction "NC_NC") (pintype "passive"))
    )
    (net (code "54") (name "Net-(HD5-Pad2)") (class "Default")
      (node (ref "HD5") (pin "2") (pinfunction "2_2") (pintype "passive"))
      (node (ref "S") (pin "1") (pinfunction "1_1") (pintype "passive"))
    )
    (net (code "55") (name "Net-(K5-PadNO)") (class "Default")
      (node (ref "K5") (pin "NO") (pinfunction "NO_NO") (pintype "passive"))
      (node (ref "R13") (pin "1") (pinfunction "1_1") (pintype "passive"))
      (node (ref "R14") (pin "1") (pinfunction "1_1") (pintype "passive"))
    )
    (net (code "56") (name "Net-(K6-PadNO)") (class "Default")
      (node (ref "K6") (pin "NO") (pinfunction "NO_NO") (pintype "passive"))
      (node (ref "R17") (pin "1") (pinfunction "1_1") (pintype "passive"))
      (node (ref "R18") (pin "1") (pinfunction "1_1") (pintype "passive"))
    )
    (net (code "57") (name "Net-(LED1-Pad1)") (class "Default")
      (node (ref "LED1") (pin "1") (pinfunction "1_1") (pintype "passive"))
      (node (ref "R1") (pin "1") (pinfunction "1_1") (pintype "passive"))
    )
    (net (code "58") (name "Net-(LED2-Pad1)") (class "Default")
      (node (ref "LED2") (pin "1") (pinfunction "1_1") (pintype "passive"))
      (node (ref "R2") (pin "1") (pinfunction "1_1") (pintype "passive"))
    )
    (net (code "59") (name "Net-(Q1-B)") (class "Default")
      (node (ref "Q1") (pin "3") (pinfunction "B_3") (pintype "passive"))
      (node (ref "R4") (pin "2") (pinfunction "2_2") (pintype "passive"))
    )
    (net (code "60") (name "Net-(Q2-B)") (class "Default")
      (node (ref "Q2") (pin "3") (pinfunction "B_3") (pintype "passive"))
      (node (ref "R6") (pin "2") (pinfunction "2_2") (pintype "passive"))
    )
    (net (code "61") (name "Net-(Q3-B)") (class "Default")
      (node (ref "Q3") (pin "3") (pinfunction "B_3") (pintype "passive"))
      (node (ref "R8") (pin "2") (pinfunction "2_2") (pintype "passive"))
    )
    (net (code "62") (name "Net-(Q4-B)") (class "Default")
      (node (ref "Q4") (pin "3") (pinfunction "B_3") (pintype "passive"))
      (node (ref "R10") (pin "2") (pinfunction "2_2") (pintype "passive"))
    )
    (net (code "63") (name "Net-(Q5-B)") (class "Default")
      (node (ref "Q5") (pin "3") (pinfunction "B_3") (pintype "passive"))
      (node (ref "R12") (pin "2") (pinfunction "2_2") (pintype "passive"))
    )
    (net (code "64") (name "Net-(Q6-B)") (class "Default")
      (node (ref "Q6") (pin "3") (pinfunction "B_3") (pintype "passive"))
      (node (ref "R16") (pin "2") (pinfunction "2_2") (pintype "passive"))
    )
    (net (code "65") (name "Net-(Q7-B)") (class "Default")
      (node (ref "Q7") (pin "3") (pinfunction "B_3") (pintype "passive"))
      (node (ref "R20") (pin "2") (pinfunction "2_2") (pintype "passive"))
    )
    (net (code "66") (name "Net-(U2-A)") (class "Default")
      (node (ref "R3") (pin "1") (pinfunction "1_1") (pintype "passive"))
      (node (ref "U2") (pin "1") (pinfunction "A_1") (pintype "passive"))
    )
    (net (code "67") (name "Net-(U2-E)") (class "Default")
      (node (ref "R4") (pin "1") (pinfunction "1_1") (pintype "passive"))
      (node (ref "U2") (pin "3") (pinfunction "E_3") (pintype "passive"))
    )
    (net (code "68") (name "Net-(U2-K)") (class "Default")
      (node (ref "LED3") (pin "1") (pinfunction "1_1") (pintype "passive"))
      (node (ref "U2") (pin "2") (pinfunction "K_2") (pintype "passive"))
    )
    (net (code "69") (name "Net-(U3-A)") (class "Default")
      (node (ref "R5") (pin "1") (pinfunction "1_1") (pintype "passive"))
      (node (ref "U3") (pin "1") (pinfunction "A_1") (pintype "passive"))
    )
    (net (code "70") (name "Net-(U3-E)") (class "Default")
      (node (ref "R6") (pin "1") (pinfunction "1_1") (pintype "passive"))
      (node (ref "U3") (pin "3") (pinfunction "E_3") (pintype "passive"))
    )
    (net (code "71") (name "Net-(U3-K)") (class "Default")
      (node (ref "LED4") (pin "1") (pinfunction "1_1") (pintype "passive"))
      (node (ref "U3") (pin "2") (pinfunction "K_2") (pintype "passive"))
    )
    (net (code "72") (name "Net-(U4-A)") (class "Default")
      (node (ref "R7") (pin "1") (pinfunction "1_1") (pintype "passive"))
      (node (ref "U4") (pin "1") (pinfunction "A_1") (pintype "passive"))
    )
    (net (code "73") (name "Net-(U4-E)") (class "Default")
      (node (ref "R8") (pin "1") (pinfunction "1_1") (pintype "passive"))
      (node (ref "U4") (pin "3") (pinfunction "E_3") (pintype "passive"))
    )
    (net (code "74") (name "Net-(U4-K)") (class "Default")
      (node (ref "LED5") (pin "1") (pinfunction "1_1") (pintype "passive"))
      (node (ref "U4") (pin "2") (pinfunction "K_2") (pintype "passive"))
    )
    (net (code "75") (name "Net-(U5-A)") (class "Default")
      (node (ref "R9") (pin "1") (pinfunction "1_1") (pintype "passive"))
      (node (ref "U5") (pin "1") (pinfunction "A_1") (pintype "passive"))
    )
    (net (code "76") (name "Net-(U5-E)") (class "Default")
      (node (ref "R10") (pin "1") (pinfunction "1_1") (pintype "passive"))
      (node (ref "U5") (pin "3") (pinfunction "E_3") (pintype "passive"))
    )
    (net (code "77") (name "Net-(U5-K)") (class "Default")
      (node (ref "LED6") (pin "1") (pinfunction "1_1") (pintype "passive"))
      (node (ref "U5") (pin "2") (pinfunction "K_2") (pintype "passive"))
    )
    (net (code "78") (name "Net-(U6-A)") (class "Default")
      (node (ref "R11") (pin "2") (pinfunction "2_2") (pintype "passive"))
      (node (ref "U6") (pin "1") (pinfunction "A_1") (pintype "passive"))
    )
    (net (code "79") (name "Net-(U6-E)") (class "Default")
      (node (ref "R12") (pin "1") (pinfunction "1_1") (pintype "passive"))
      (node (ref "U6") (pin "3") (pinfunction "E_3") (pintype "passive"))
    )
    (net (code "80") (name "Net-(U6-K)") (class "Default")
      (node (ref "LED7") (pin "1") (pinfunction "1_1") (pintype "passive"))
      (node (ref "U6") (pin "2") (pinfunction "K_2") (pintype "passive"))
    )
    (net (code "81") (name "Net-(U7-A)") (class "Default")
      (node (ref "R15") (pin "2") (pinfunction "2_2") (pintype "passive"))
      (node (ref "U7") (pin "1") (pinfunction "A_1") (pintype "passive"))
    )
    (net (code "82") (name "Net-(U7-E)") (class "Default")
      (node (ref "R16") (pin "1") (pinfunction "1_1") (pintype "passive"))
      (node (ref "U7") (pin "3") (pinfunction "E_3") (pintype "passive"))
    )
    (net (code "83") (name "Net-(U7-K)") (class "Default")
      (node (ref "LED8") (pin "1") (pinfunction "1_1") (pintype "passive"))
      (node (ref "U7") (pin "2") (pinfunction "K_2") (pintype "passive"))
    )
    (net (code "84") (name "Net-(U8-A)") (class "Default")
      (node (ref "R19") (pin "2") (pinfunction "2_2") (pintype "passive"))
      (node (ref "U8") (pin "1") (pinfunction "A_1") (pintype "passive"))
    )
    (net (code "85") (name "Net-(U8-E)") (class "Default")
      (node (ref "R20") (pin "1") (pinfunction "1_1") (pintype "passive"))
      (node (ref "U8") (pin "3") (pinfunction "E_3") (pintype "passive"))
    )
    (net (code "86") (name "Net-(U8-K)") (class "Default")
      (node (ref "LED9") (pin "1") (pinfunction "1_1") (pintype "passive"))
      (node (ref "U8") (pin "2") (pinfunction "K_2") (pintype "passive"))
    )
    (net (code "87") (name "unconnected-(C8-Pad3)") (class "Default")
      (node (ref "C8") (pin "3") (pinfunction "3_3") (pintype "passive"))
    )
    (net (code "88") (name "unconnected-(HD6-Pad3)") (class "Default")
      (node (ref "HD6") (pin "3") (pinfunction "3_3") (pintype "passive"))
    )
    (net (code "89") (name "unconnected-(K5-PadNC)") (class "Default")
      (node (ref "K5") (pin "NC") (pinfunction "NC_NC") (pintype "passive"))
    )
    (net (code "90") (name "unconnected-(K6-PadNC)") (class "Default")
      (node (ref "K6") (pin "NC") (pinfunction "NC_NC") (pintype "passive"))
    )
    (net (code "91") (name "unconnected-(K7-PadNC)") (class "Default")
      (node (ref "K7") (pin "NC") (pinfunction "NC_NC") (pintype "passive"))
    )
    (net (code "92") (name "unconnected-(S-Pad3)") (class "Default")
      (node (ref "S") (pin "3") (pinfunction "3_3") (pintype "passive"))
    )
  )
)
